# SW6124_C_LED.net
KiCad netlist of a schematic drawn in Altium Designer
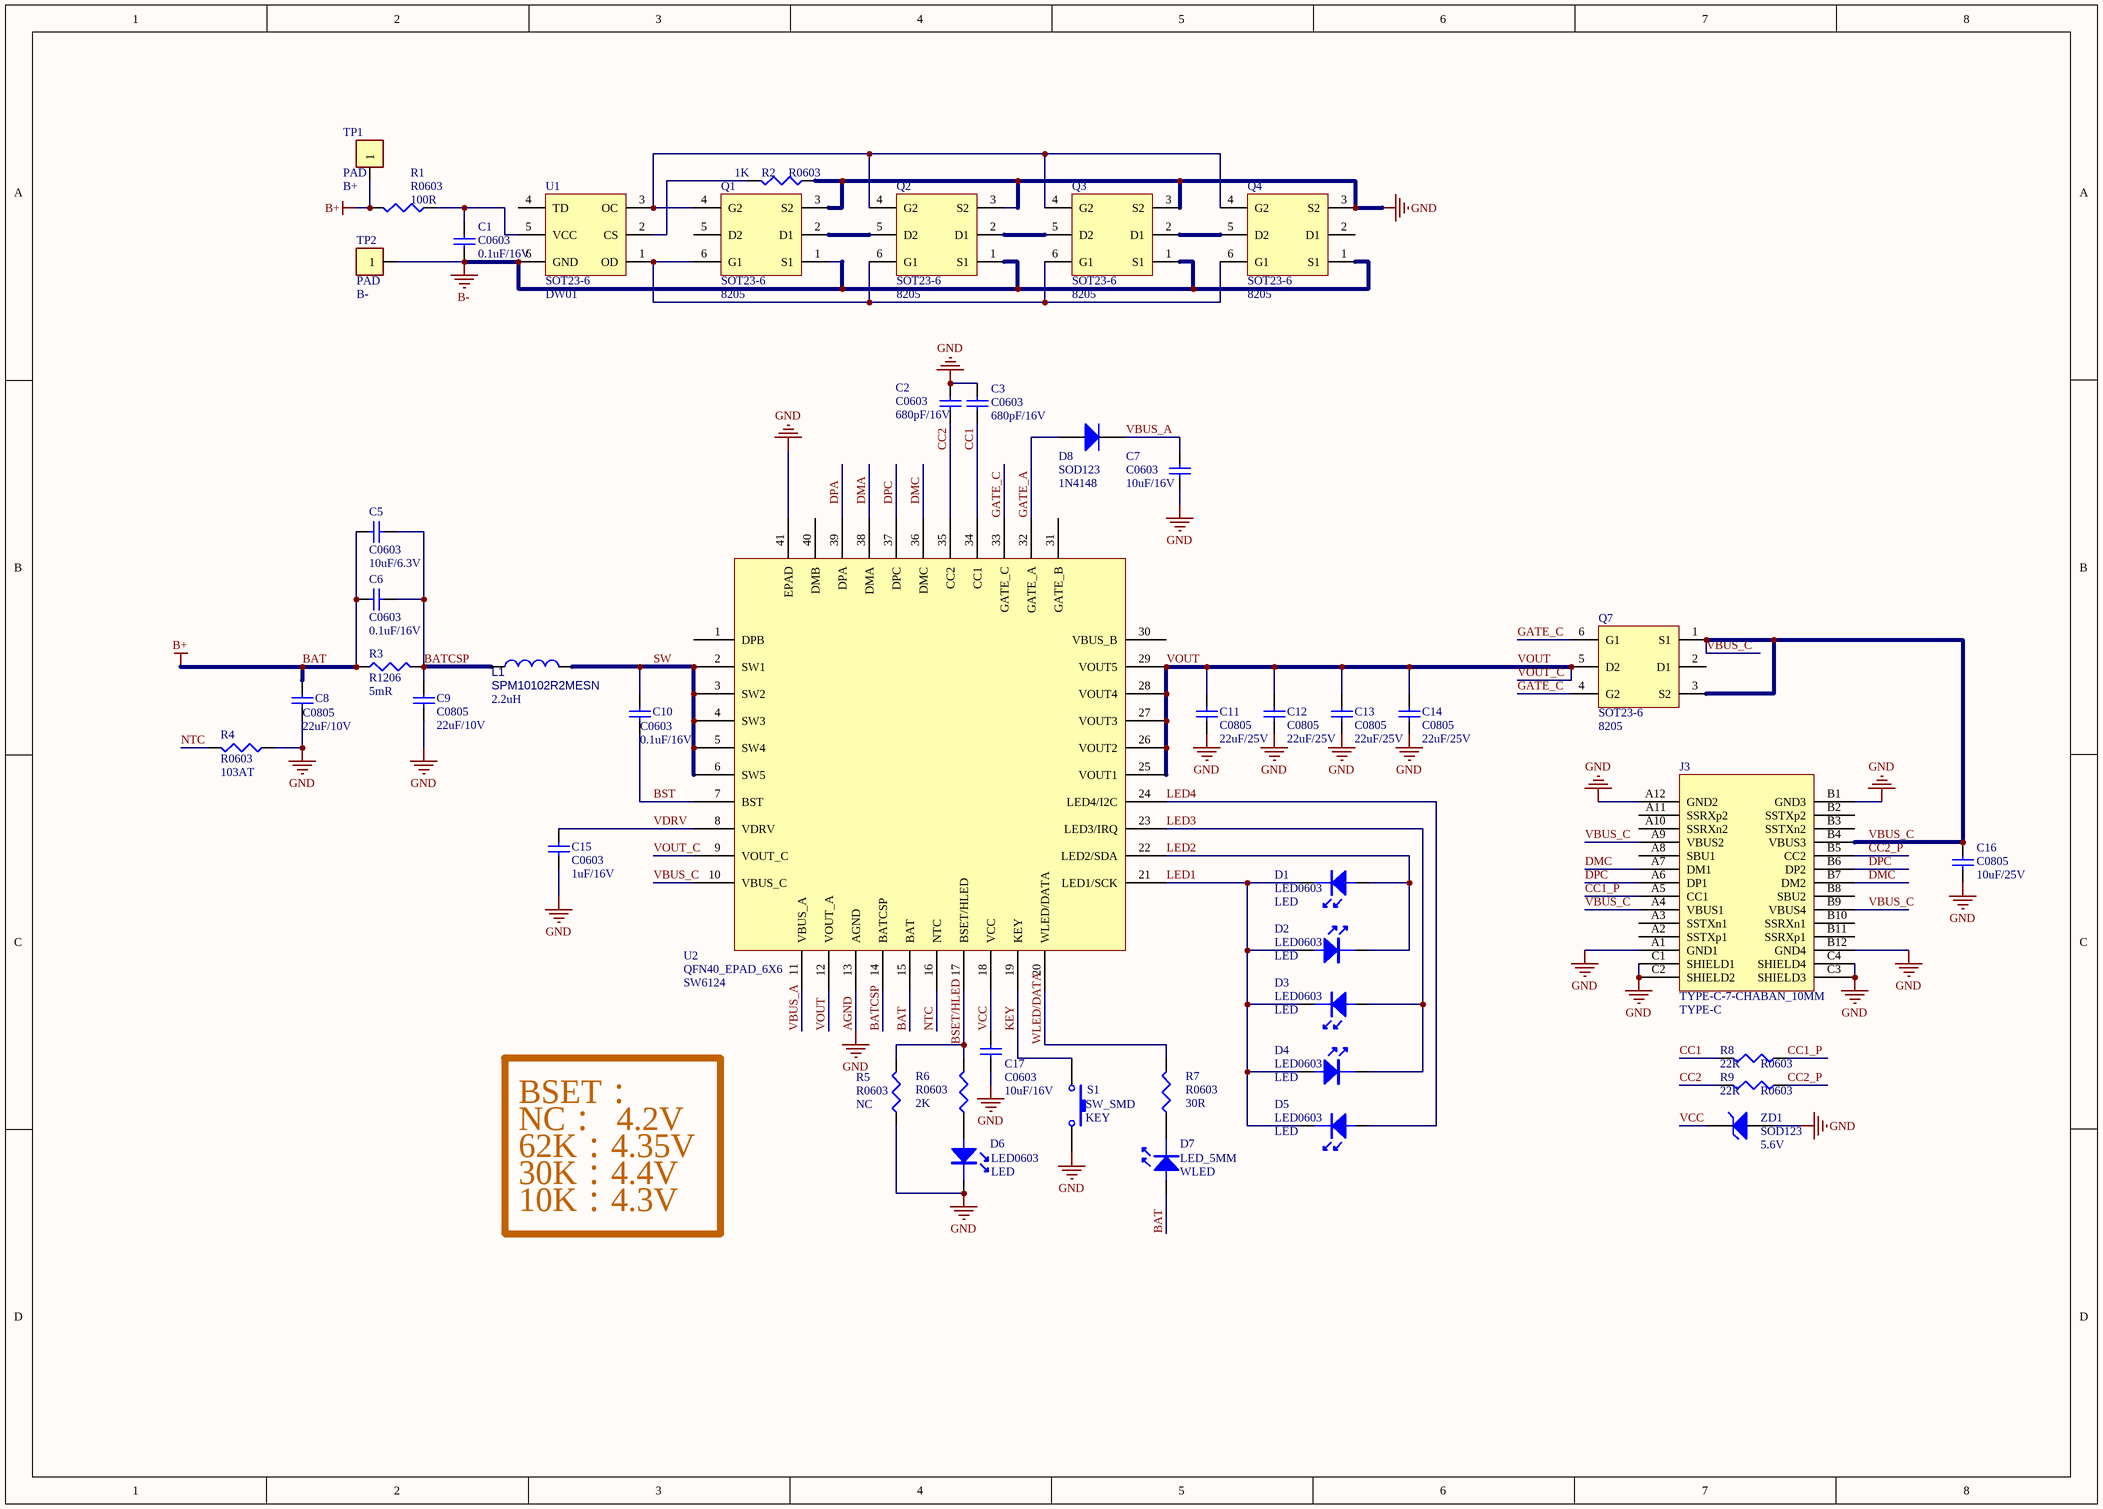
[diagram p0: SW6124+C+LED.SchDoc]

(export (version "E")
  (design (tool "Eeschema 10.0.6"))
  (components
    (comp (ref "C1")
      (value "C0603")
      (footprint "C0603")
      (description "Capacitor")
      (fields (field (name "ALTIUM_VALUE") "0.1uF/16V") (field (name "PUBLISHER") "Altium Limited"))
      (libsource (lib "*") (part "Cap"))
    )
    (comp (ref "C2")
      (value "C0603")
      (footprint "C0603")
      (description "Capacitor")
      (fields (field (name "ALTIUM_VALUE") "680pF/16V") (field (name "PUBLISHER") "Altium Limited"))
      (libsource (lib "*") (part "CAP0603"))
    )
    (comp (ref "C3")
      (value "C0603")
      (footprint "C0603")
      (description "Capacitor")
      (fields (field (name "ALTIUM_VALUE") "680pF/16V") (field (name "PUBLISHER") "Altium Limited"))
      (libsource (lib "*") (part "CAP0603"))
    )
    (comp (ref "C5")
      (value "C0603")
      (footprint "C0603")
      (description "Capacitor")
      (fields (field (name "ALTIUM_VALUE") "10uF/6.3V") (field (name "PUBLISHER") "Altium Limited"))
      (libsource (lib "*") (part "CAP0603"))
    )
    (comp (ref "C6")
      (value "C0603")
      (footprint "C0603")
      (description "Capacitor")
      (fields (field (name "ALTIUM_VALUE") "0.1uF/16V") (field (name "PUBLISHER") "Altium Limited"))
      (libsource (lib "*") (part "CAP0603"))
    )
    (comp (ref "C7")
      (value "C0603")
      (footprint "C0603")
      (description "Capacitor")
      (fields (field (name "ALTIUM_VALUE") "10uF/16V") (field (name "PUBLISHER") "Altium Limited"))
      (libsource (lib "*") (part "CAP0603"))
    )
    (comp (ref "C8")
      (value "C0805")
      (footprint "C0805")
      (description "Capacitor")
      (fields (field (name "ALTIUM_VALUE") "22uF/10V") (field (name "PUBLISHER") "Altium Limited"))
      (libsource (lib "*") (part "CAP0805"))
    )
    (comp (ref "C9")
      (value "C0805")
      (footprint "C0805")
      (description "Capacitor")
      (fields (field (name "ALTIUM_VALUE") "22uF/10V") (field (name "PUBLISHER") "Altium Limited"))
      (libsource (lib "*") (part "CAP0805"))
    )
    (comp (ref "C10")
      (value "C0603")
      (footprint "C0603")
      (description "Capacitor")
      (fields (field (name "ALTIUM_VALUE") "0.1uF/16V") (field (name "PUBLISHER") "Altium Limited"))
      (libsource (lib "*") (part "CAP0603"))
    )
    (comp (ref "C11")
      (value "C0805")
      (footprint "C0805")
      (description "Capacitor")
      (fields (field (name "ALTIUM_VALUE") "22uF/25V") (field (name "PUBLISHER") "Altium Limited"))
      (libsource (lib "*") (part "CAP0805"))
    )
    (comp (ref "C12")
      (value "C0805")
      (footprint "C0805")
      (description "Capacitor")
      (fields (field (name "ALTIUM_VALUE") "22uF/25V") (field (name "PUBLISHER") "Altium Limited"))
      (libsource (lib "*") (part "CAP0805"))
    )
    (comp (ref "C13")
      (value "C0805")
      (footprint "C0805")
      (description "Capacitor")
      (fields (field (name "ALTIUM_VALUE") "22uF/25V") (field (name "PUBLISHER") "Altium Limited"))
      (libsource (lib "*") (part "CAP0805"))
    )
    (comp (ref "C14")
      (value "C0805")
      (footprint "C0805")
      (description "Capacitor")
      (fields (field (name "ALTIUM_VALUE") "22uF/25V") (field (name "PUBLISHER") "Altium Limited"))
      (libsource (lib "*") (part "CAP0805"))
    )
    (comp (ref "C15")
      (value "C0603")
      (footprint "C0603")
      (description "Capacitor")
      (fields (field (name "ALTIUM_VALUE") "1uF/16V") (field (name "PUBLISHER") "Altium Limited"))
      (libsource (lib "*") (part "CAP0603"))
    )
    (comp (ref "C16")
      (value "C0805")
      (footprint "C0805")
      (description "Capacitor")
      (fields (field (name "ALTIUM_VALUE") "10uF/25V") (field (name "PUBLISHER") "Altium Limited"))
      (libsource (lib "*") (part "CAP0603"))
    )
    (comp (ref "C17")
      (value "C0603")
      (footprint "C0603")
      (description "Capacitor")
      (fields (field (name "ALTIUM_VALUE") "10uF/16V") (field (name "PUBLISHER") "Altium Limited"))
      (libsource (lib "*") (part "CAP0603"))
    )
    (comp (ref "D1") (value "LED") (footprint "LED0603") (libsource (lib "*") (part "LED")))
    (comp (ref "D2") (value "LED") (footprint "LED0603") (libsource (lib "*") (part "LED")))
    (comp (ref "D3") (value "LED") (footprint "LED0603") (libsource (lib "*") (part "LED")))
    (comp (ref "D4") (value "LED") (footprint "LED0603") (libsource (lib "*") (part "LED")))
    (comp (ref "D5") (value "LED") (footprint "LED0603") (libsource (lib "*") (part "LED")))
    (comp (ref "D6") (value "LED") (footprint "LED0603") (libsource (lib "*") (part "LED")))
    (comp (ref "D7")
      (value "WLED")
      (footprint "LED_5MM")
      (fields (field (name "FOOTPRINF") "LED_5MM") (field (name "Comment") "LED_5MM"))
      (libsource (lib "*") (part "LED"))
    )
    (comp (ref "D8")
      (value "1N4148")
      (footprint "SOD123")
      (description "High Conductance Fast Diode")
      (fields (field (name "Comment") "Diode 1N4148") (field (name "PUBLISHER") "Altium Limited"))
      (libsource (lib "Miscellaneous Devices") (part "Diode 1N4148"))
    )
    (comp (ref "J3")
      (value "TYPE-C")
      (footprint "TYPE-C-7-CHABAN_10MM")
      (libsource (lib "*") (part "TYPE-C"))
    )
    (comp (ref "L1")
      (value "SPM10102R2MESN")
      (footprint "INDUCTOR_SPM1010")
      (fields (field (name "ALTIUM_VALUE") "2.2uH"))
      (libsource (lib "*") (part "INDUCTOR"))
    )
    (comp (ref "Q1")
      (value "8205")
      (footprint "SOT23-6")
      (fields (field (name "FOOTPRINF") "SOT23-6"))
      (libsource (lib "") (part "8205B_1"))
    )
    (comp (ref "Q2")
      (value "8205")
      (footprint "SOT23-6")
      (fields (field (name "FOOTPRINF") "SOT23-6"))
      (libsource (lib "") (part "8205B_1"))
    )
    (comp (ref "Q3")
      (value "8205")
      (footprint "SOT23-6")
      (fields (field (name "FOOTPRINF") "SOT23-6"))
      (libsource (lib "") (part "8205B_1"))
    )
    (comp (ref "Q4")
      (value "8205")
      (footprint "SOT23-6")
      (fields (field (name "FOOTPRINF") "SOT23-6"))
      (libsource (lib "") (part "8205B_1"))
    )
    (comp (ref "Q7")
      (value "8205")
      (footprint "SOT23-6")
      (fields (field (name "FOOTPRINF") "SOT23-6"))
      (libsource (lib "*") (part "8205B"))
    )
    (comp (ref "R1")
      (value "R0603")
      (footprint "R0603")
      (description "Resistor")
      (fields (field (name "ALTIUM_VALUE") "100R") (field (name "PUBLISHER") "Altium Limited"))
      (libsource (lib "*") (part "Res3"))
    )
    (comp (ref "R2")
      (value "R0603")
      (footprint "R0603")
      (description "Resistor")
      (fields (field (name "ALTIUM_VALUE") "1K") (field (name "PUBLISHER") "Altium Limited"))
      (libsource (lib "*") (part "Res3"))
    )
    (comp (ref "R3")
      (value "R1206")
      (footprint "R1206")
      (description "Resistor")
      (fields (field (name "ALTIUM_VALUE") "5mR") (field (name "PUBLISHER") "Altium Limited"))
      (libsource (lib "*") (part "RES"))
    )
    (comp (ref "R4")
      (value "R0603")
      (footprint "R0603")
      (description "Resistor")
      (fields (field (name "ALTIUM_VALUE") "103AT") (field (name "PUBLISHER") "Altium Limited"))
      (libsource (lib "*") (part "RES"))
    )
    (comp (ref "R5")
      (value "R0603")
      (footprint "R0603")
      (description "Resistor")
      (fields (field (name "ALTIUM_VALUE") "NC") (field (name "PUBLISHER") "Altium Limited"))
      (libsource (lib "*") (part "RES"))
    )
    (comp (ref "R6")
      (value "R0603")
      (footprint "R0603")
      (description "Resistor")
      (fields (field (name "ALTIUM_VALUE") "2K") (field (name "PUBLISHER") "Altium Limited"))
      (libsource (lib "*") (part "RES"))
    )
    (comp (ref "R7")
      (value "R0603")
      (footprint "R0603")
      (description "Resistor")
      (fields (field (name "ALTIUM_VALUE") "30R") (field (name "PUBLISHER") "Altium Limited"))
      (libsource (lib "*") (part "RES"))
    )
    (comp (ref "R8")
      (value "R0603")
      (footprint "R0603")
      (description "Resistor")
      (fields (field (name "ALTIUM_VALUE") "22R") (field (name "PUBLISHER") "Altium Limited"))
      (libsource (lib "*") (part "RES"))
    )
    (comp (ref "R9")
      (value "R0603")
      (footprint "R0603")
      (description "Resistor")
      (fields (field (name "ALTIUM_VALUE") "22R") (field (name "PUBLISHER") "Altium Limited"))
      (libsource (lib "*") (part "RES"))
    )
    (comp (ref "S1")
      (value "KEY")
      (footprint "SW_SMD")
      (fields (field (name "FOOTPRINF") "SW_SMD"))
      (libsource (lib "*") (part "SW K"))
    )
    (comp (ref "TP1") (value "B+") (footprint "PAD") (libsource (lib "*") (part "Test Point")))
    (comp (ref "TP2") (value "B-") (footprint "PAD") (libsource (lib "") (part "Test Point_1")))
    (comp (ref "U1")
      (value "DW01")
      (footprint "SOT23-6")
      (fields (field (name "FOOTPRINF") "SOT23-6"))
      (libsource (lib "*") (part "DW01"))
    )
    (comp (ref "U2")
      (value "SW6124")
      (footprint "QFN40_EPAD_6X6")
      (libsource (lib "TEST") (part "SW6106_AFC"))
    )
    (comp (ref "ZD1")
      (value "SOD123")
      (footprint "SOD-123")
      (description "Zener Diode")
      (fields (field (name "ALTIUM_UNNAMED_1") "5.6V"))
      (libsource (lib "Miscellaneous Devices") (part "D Zener"))
    )
  )
  (nets
    (net (code "1") (name "/BATCSP") (class "Default")
      (node (ref "C5") (pin "2") (pinfunction "2_2") (pintype "passive"))
      (node (ref "C6") (pin "2") (pinfunction "2_2") (pintype "passive"))
      (node (ref "C9") (pin "2") (pinfunction "2_2") (pintype "passive"))
      (node (ref "L1") (pin "1") (pinfunction "1_1") (pintype "passive"))
      (node (ref "R3") (pin "2") (pinfunction "2_2") (pintype "passive"))
      (node (ref "U2") (pin "14") (pinfunction "BATCSP_14") (pintype "passive"))
    )
    (net (code "2") (name "/BSET{slash}HLED") (class "Default")
      (node (ref "R5") (pin "2") (pinfunction "2_2") (pintype "passive"))
      (node (ref "R6") (pin "2") (pinfunction "2_2") (pintype "passive"))
      (node (ref "U2") (pin "17") (pinfunction "BSET/HLED_17") (pintype "passive"))
    )
    (net (code "3") (name "/BST") (class "Default")
      (node (ref "C10") (pin "1") (pinfunction "1_1") (pintype "passive"))
      (node (ref "U2") (pin "7") (pinfunction "BST_7") (pintype "passive"))
    )
    (net (code "4") (name "/CC1") (class "Default")
      (node (ref "C3") (pin "1") (pinfunction "1_1") (pintype "passive"))
      (node (ref "R8") (pin "2") (pinfunction "2_2") (pintype "passive"))
      (node (ref "U2") (pin "34") (pinfunction "CC1_34") (pintype "passive"))
    )
    (net (code "5") (name "/CC1_P") (class "Default")
      (node (ref "J3") (pin "A5") (pinfunction "CC1_A5") (pintype "passive"))
      (node (ref "R8") (pin "1") (pinfunction "1_1") (pintype "passive"))
    )
    (net (code "6") (name "/CC2") (class "Default")
      (node (ref "C2") (pin "1") (pinfunction "1_1") (pintype "passive"))
      (node (ref "R9") (pin "2") (pinfunction "2_2") (pintype "passive"))
      (node (ref "U2") (pin "35") (pinfunction "CC2_35") (pintype "passive"))
    )
    (net (code "7") (name "/CC2_P") (class "Default")
      (node (ref "J3") (pin "B5") (pinfunction "CC2_B5") (pintype "passive"))
      (node (ref "R9") (pin "1") (pinfunction "1_1") (pintype "passive"))
    )
    (net (code "8") (name "/DMA") (class "Default")
      (node (ref "U2") (pin "38") (pinfunction "DMA_38") (pintype "passive"))
    )
    (net (code "9") (name "/DMC") (class "Default")
      (node (ref "J3") (pin "A7") (pinfunction "DM1_A7") (pintype "passive"))
      (node (ref "J3") (pin "B7") (pinfunction "DM2_B7") (pintype "passive"))
      (node (ref "U2") (pin "36") (pinfunction "DMC_36") (pintype "passive"))
    )
    (net (code "10") (name "/DPA") (class "Default")
      (node (ref "U2") (pin "39") (pinfunction "DPA_39") (pintype "passive"))
    )
    (net (code "11") (name "/DPC") (class "Default")
      (node (ref "J3") (pin "A6") (pinfunction "DP1_A6") (pintype "passive"))
      (node (ref "J3") (pin "B6") (pinfunction "DP2_B6") (pintype "passive"))
      (node (ref "U2") (pin "37") (pinfunction "DPC_37") (pintype "passive"))
    )
    (net (code "12") (name "/GATE_A") (class "Default")
      (node (ref "D8") (pin "1") (pinfunction "A_1") (pintype "passive"))
      (node (ref "U2") (pin "32") (pinfunction "GATE_A_32") (pintype "passive"))
    )
    (net (code "13") (name "/GATE_C") (class "Default")
      (node (ref "Q7") (pin "4") (pinfunction "G2_4") (pintype "passive"))
      (node (ref "Q7") (pin "6") (pinfunction "G1_6") (pintype "passive"))
      (node (ref "U2") (pin "33") (pinfunction "GATE_C_33") (pintype "passive"))
    )
    (net (code "14") (name "/KEY") (class "Default")
      (node (ref "S1") (pin "1") (pinfunction "1_1") (pintype "passive"))
      (node (ref "U2") (pin "19") (pinfunction "KEY_19") (pintype "passive"))
    )
    (net (code "15") (name "/LED1") (class "Default")
      (node (ref "D1") (pin "2") (pinfunction "K_2") (pintype "passive"))
      (node (ref "D2") (pin "1") (pinfunction "A_1") (pintype "passive"))
      (node (ref "D3") (pin "2") (pinfunction "K_2") (pintype "passive"))
      (node (ref "D4") (pin "1") (pinfunction "A_1") (pintype "passive"))
      (node (ref "D5") (pin "2") (pinfunction "K_2") (pintype "passive"))
      (node (ref "U2") (pin "21") (pinfunction "LED1/SCK_21") (pintype "passive"))
    )
    (net (code "16") (name "/LED2") (class "Default")
      (node (ref "D1") (pin "1") (pinfunction "A_1") (pintype "passive"))
      (node (ref "D2") (pin "2") (pinfunction "K_2") (pintype "passive"))
      (node (ref "U2") (pin "22") (pinfunction "LED2/SDA_22") (pintype "passive"))
    )
    (net (code "17") (name "/LED3") (class "Default")
      (node (ref "D3") (pin "1") (pinfunction "A_1") (pintype "passive"))
      (node (ref "D4") (pin "2") (pinfunction "K_2") (pintype "passive"))
      (node (ref "U2") (pin "23") (pinfunction "LED3/IRQ_23") (pintype "passive"))
    )
    (net (code "18") (name "/LED4") (class "Default")
      (node (ref "D5") (pin "1") (pinfunction "A_1") (pintype "passive"))
      (node (ref "U2") (pin "24") (pinfunction "LED4/I2C_24") (pintype "passive"))
    )
    (net (code "19") (name "/NTC") (class "Default")
      (node (ref "R4") (pin "2") (pinfunction "2_2") (pintype "passive"))
      (node (ref "U2") (pin "16") (pinfunction "NTC_16") (pintype "passive"))
    )
    (net (code "20") (name "/SW") (class "Default")
      (node (ref "C10") (pin "2") (pinfunction "2_2") (pintype "passive"))
      (node (ref "L1") (pin "2") (pinfunction "2_2") (pintype "passive"))
      (node (ref "U2") (pin "2") (pinfunction "SW1_2") (pintype "passive"))
      (node (ref "U2") (pin "3") (pinfunction "SW2_3") (pintype "passive"))
      (node (ref "U2") (pin "4") (pinfunction "SW3_4") (pintype "passive"))
      (node (ref "U2") (pin "5") (pinfunction "SW4_5") (pintype "passive"))
      (node (ref "U2") (pin "6") (pinfunction "SW5_6") (pintype "passive"))
    )
    (net (code "21") (name "/VBUS_A") (class "Default")
      (node (ref "C7") (pin "2") (pinfunction "2_2") (pintype "passive"))
      (node (ref "D8") (pin "2") (pinfunction "K_2") (pintype "passive"))
      (node (ref "U2") (pin "11") (pinfunction "VBUS_A_11") (pintype "passive"))
    )
    (net (code "22") (name "/VBUS_C") (class "Default")
      (node (ref "C16") (pin "2") (pinfunction "2_2") (pintype "passive"))
      (node (ref "J3") (pin "A4") (pinfunction "VBUS1_A4") (pintype "passive"))
      (node (ref "J3") (pin "A9") (pinfunction "VBUS2_A9") (pintype "passive"))
      (node (ref "J3") (pin "B4") (pinfunction "VBUS3_B4") (pintype "passive"))
      (node (ref "J3") (pin "B9") (pinfunction "VBUS4_B9") (pintype "passive"))
      (node (ref "Q7") (pin "1") (pinfunction "S1_1") (pintype "passive"))
      (node (ref "Q7") (pin "3") (pinfunction "S2_3") (pintype "passive"))
      (node (ref "U2") (pin "10") (pinfunction "VBUS_C_10") (pintype "passive"))
    )
    (net (code "23") (name "/VCC") (class "Default")
      (node (ref "C17") (pin "2") (pinfunction "2_2") (pintype "passive"))
      (node (ref "U2") (pin "18") (pinfunction "VCC_18") (pintype "passive"))
      (node (ref "ZD1") (pin "2") (pinfunction "K_2") (pintype "passive"))
    )
    (net (code "24") (name "/VDRV") (class "Default")
      (node (ref "C15") (pin "2") (pinfunction "2_2") (pintype "passive"))
      (node (ref "U2") (pin "8") (pinfunction "VDRV_8") (pintype "passive"))
    )
    (net (code "25") (name "/VOUT") (class "Default")
      (node (ref "C11") (pin "2") (pinfunction "2_2") (pintype "passive"))
      (node (ref "C12") (pin "2") (pinfunction "2_2") (pintype "passive"))
      (node (ref "C13") (pin "2") (pinfunction "2_2") (pintype "passive"))
      (node (ref "C14") (pin "2") (pinfunction "2_2") (pintype "passive"))
      (node (ref "Q7") (pin "5") (pinfunction "D2_5") (pintype "passive"))
      (node (ref "U2") (pin "12") (pinfunction "VOUT_A_12") (pintype "passive"))
      (node (ref "U2") (pin "25") (pinfunction "VOUT1_25") (pintype "passive"))
      (node (ref "U2") (pin "26") (pinfunction "VOUT2_26") (pintype "passive"))
      (node (ref "U2") (pin "27") (pinfunction "VOUT3_27") (pintype "passive"))
      (node (ref "U2") (pin "28") (pinfunction "VOUT4_28") (pintype "passive"))
      (node (ref "U2") (pin "29") (pinfunction "VOUT5_29") (pintype "passive"))
      (node (ref "U2") (pin "9") (pinfunction "VOUT_C_9") (pintype "passive"))
    )
    (net (code "26") (name "/WLED{slash}DATA") (class "Default")
      (node (ref "R7") (pin "2") (pinfunction "2_2") (pintype "passive"))
      (node (ref "U2") (pin "20") (pinfunction "WLED/DATA_20") (pintype "passive"))
    )
    (net (code "27") (name "B+") (class "Default")
      (node (ref "C5") (pin "1") (pinfunction "1_1") (pintype "passive"))
      (node (ref "C6") (pin "1") (pinfunction "1_1") (pintype "passive"))
      (node (ref "C8") (pin "2") (pinfunction "2_2") (pintype "passive"))
      (node (ref "D7") (pin "1") (pinfunction "A_1") (pintype "passive"))
      (node (ref "R1") (pin "2") (pinfunction "2_2") (pintype "passive"))
      (node (ref "R3") (pin "1") (pinfunction "1_1") (pintype "passive"))
      (node (ref "TP1") (pin "1") (pinfunction "1_1") (pintype "passive"))
      (node (ref "U2") (pin "15") (pinfunction "BAT_15") (pintype "passive"))
    )
    (net (code "28") (name "B-") (class "Default")
      (node (ref "C1") (pin "1") (pinfunction "1_1") (pintype "passive"))
      (node (ref "Q1") (pin "1") (pinfunction "S1_1") (pintype "passive"))
      (node (ref "Q2") (pin "1") (pinfunction "S1_1") (pintype "passive"))
      (node (ref "Q3") (pin "1") (pinfunction "S1_1") (pintype "passive"))
      (node (ref "Q4") (pin "1") (pinfunction "S1_1") (pintype "passive"))
      (node (ref "TP2") (pin "1") (pinfunction "1_1") (pintype "passive"))
      (node (ref "U1") (pin "6") (pinfunction "GND_6") (pintype "passive"))
    )
    (net (code "29") (name "GND") (class "Default")
      (node (ref "C11") (pin "1") (pinfunction "1_1") (pintype "passive"))
      (node (ref "C12") (pin "1") (pinfunction "1_1") (pintype "passive"))
      (node (ref "C13") (pin "1") (pinfunction "1_1") (pintype "passive"))
      (node (ref "C14") (pin "1") (pinfunction "1_1") (pintype "passive"))
      (node (ref "C15") (pin "1") (pinfunction "1_1") (pintype "passive"))
      (node (ref "C16") (pin "1") (pinfunction "1_1") (pintype "passive"))
      (node (ref "C17") (pin "1") (pinfunction "1_1") (pintype "passive"))
      (node (ref "C2") (pin "2") (pinfunction "2_2") (pintype "passive"))
      (node (ref "C3") (pin "2") (pinfunction "2_2") (pintype "passive"))
      (node (ref "C7") (pin "1") (pinfunction "1_1") (pintype "passive"))
      (node (ref "C8") (pin "1") (pinfunction "1_1") (pintype "passive"))
      (node (ref "C9") (pin "1") (pinfunction "1_1") (pintype "passive"))
      (node (ref "D6") (pin "2") (pinfunction "K_2") (pintype "passive"))
      (node (ref "J3") (pin "A1") (pinfunction "GND1_A1") (pintype "passive"))
      (node (ref "J3") (pin "A12") (pinfunction "GND2_A12") (pintype "passive"))
      (node (ref "J3") (pin "B1") (pinfunction "GND3_B1") (pintype "passive"))
      (node (ref "J3") (pin "B12") (pinfunction "GND4_B12") (pintype "passive"))
      (node (ref "J3") (pin "C1") (pinfunction "SHIELD1_C1") (pintype "passive"))
      (node (ref "J3") (pin "C2") (pinfunction "SHIELD2_C2") (pintype "passive"))
      (node (ref "J3") (pin "C3") (pinfunction "SHIELD3_C3") (pintype "passive"))
      (node (ref "J3") (pin "C4") (pinfunction "SHIELD4_C4") (pintype "passive"))
      (node (ref "Q1") (pin "3") (pinfunction "S2_3") (pintype "passive"))
      (node (ref "Q2") (pin "3") (pinfunction "S2_3") (pintype "passive"))
      (node (ref "Q3") (pin "3") (pinfunction "S2_3") (pintype "passive"))
      (node (ref "Q4") (pin "3") (pinfunction "S2_3") (pintype "passive"))
      (node (ref "R2") (pin "1") (pinfunction "1_1") (pintype "passive"))
      (node (ref "R4") (pin "1") (pinfunction "1_1") (pintype "passive"))
      (node (ref "R5") (pin "1") (pinfunction "1_1") (pintype "passive"))
      (node (ref "S1") (pin "2") (pinfunction "2_2") (pintype "passive"))
      (node (ref "U2") (pin "13") (pinfunction "AGND_13") (pintype "passive"))
      (node (ref "U2") (pin "41") (pinfunction "EPAD_41") (pintype "passive"))
      (node (ref "ZD1") (pin "1") (pinfunction "A_1") (pintype "passive"))
    )
    (net (code "30") (name "Net-(D6-A)") (class "Default")
      (node (ref "D6") (pin "1") (pinfunction "A_1") (pintype "passive"))
      (node (ref "R6") (pin "1") (pinfunction "1_1") (pintype "passive"))
    )
    (net (code "31") (name "Net-(D7-K)") (class "Default")
      (node (ref "D7") (pin "2") (pinfunction "K_2") (pintype "passive"))
      (node (ref "R7") (pin "1") (pinfunction "1_1") (pintype "passive"))
    )
    (net (code "32") (name "Net-(Q1-D1)") (class "Default")
      (node (ref "Q1") (pin "2") (pinfunction "D1_2") (pintype "passive"))
      (node (ref "Q2") (pin "5") (pinfunction "D2_5") (pintype "passive"))
    )
    (net (code "33") (name "Net-(Q1-G1)") (class "Default")
      (node (ref "Q1") (pin "6") (pinfunction "G1_6") (pintype "passive"))
      (node (ref "Q2") (pin "6") (pinfunction "G1_6") (pintype "passive"))
      (node (ref "Q3") (pin "6") (pinfunction "G1_6") (pintype "passive"))
      (node (ref "Q4") (pin "6") (pinfunction "G1_6") (pintype "passive"))
      (node (ref "U1") (pin "1") (pinfunction "OD_1") (pintype "passive"))
    )
    (net (code "34") (name "Net-(Q1-G2)") (class "Default")
      (node (ref "Q1") (pin "4") (pinfunction "G2_4") (pintype "passive"))
      (node (ref "Q2") (pin "4") (pinfunction "G2_4") (pintype "passive"))
      (node (ref "Q3") (pin "4") (pinfunction "G2_4") (pintype "passive"))
      (node (ref "Q4") (pin "4") (pinfunction "G2_4") (pintype "passive"))
      (node (ref "U1") (pin "3") (pinfunction "OC_3") (pintype "passive"))
    )
    (net (code "35") (name "Net-(Q2-D1)") (class "Default")
      (node (ref "Q2") (pin "2") (pinfunction "D1_2") (pintype "passive"))
      (node (ref "Q3") (pin "5") (pinfunction "D2_5") (pintype "passive"))
    )
    (net (code "36") (name "Net-(Q3-D1)") (class "Default")
      (node (ref "Q3") (pin "2") (pinfunction "D1_2") (pintype "passive"))
      (node (ref "Q4") (pin "5") (pinfunction "D2_5") (pintype "passive"))
    )
    (net (code "37") (name "Net-(U1-CS)") (class "Default")
      (node (ref "R2") (pin "2") (pinfunction "2_2") (pintype "passive"))
      (node (ref "U1") (pin "2") (pinfunction "CS_2") (pintype "passive"))
    )
    (net (code "38") (name "Net-(U1-VCC)") (class "Default")
      (node (ref "C1") (pin "2") (pinfunction "2_2") (pintype "passive"))
      (node (ref "R1") (pin "1") (pinfunction "1_1") (pintype "passive"))
      (node (ref "U1") (pin "5") (pinfunction "VCC_5") (pintype "passive"))
    )
    (net (code "39") (name "unconnected-(J3-SBU1-PadA8)") (class "Default")
      (node (ref "J3") (pin "A8") (pinfunction "SBU1_A8") (pintype "passive"))
    )
    (net (code "40") (name "unconnected-(J3-SBU2-PadB8)") (class "Default")
      (node (ref "J3") (pin "B8") (pinfunction "SBU2_B8") (pintype "passive"))
    )
    (net (code "41") (name "unconnected-(J3-SSRXn1-PadB10)") (class "Default")
      (node (ref "J3") (pin "B10") (pinfunction "SSRXn1_B10") (pintype "passive"))
    )
    (net (code "42") (name "unconnected-(J3-SSRXn2-PadA10)") (class "Default")
      (node (ref "J3") (pin "A10") (pinfunction "SSRXn2_A10") (pintype "passive"))
    )
    (net (code "43") (name "unconnected-(J3-SSRXp1-PadB11)") (class "Default")
      (node (ref "J3") (pin "B11") (pinfunction "SSRXp1_B11") (pintype "passive"))
    )
    (net (code "44") (name "unconnected-(J3-SSRXp2-PadA11)") (class "Default")
      (node (ref "J3") (pin "A11") (pinfunction "SSRXp2_A11") (pintype "passive"))
    )
    (net (code "45") (name "unconnected-(J3-SSTXn1-PadA3)") (class "Default")
      (node (ref "J3") (pin "A3") (pinfunction "SSTXn1_A3") (pintype "passive"))
    )
    (net (code "46") (name "unconnected-(J3-SSTXn2-PadB3)") (class "Default")
      (node (ref "J3") (pin "B3") (pinfunction "SSTXn2_B3") (pintype "passive"))
    )
    (net (code "47") (name "unconnected-(J3-SSTXp1-PadA2)") (class "Default")
      (node (ref "J3") (pin "A2") (pinfunction "SSTXp1_A2") (pintype "passive"))
    )
    (net (code "48") (name "unconnected-(J3-SSTXp2-PadB2)") (class "Default")
      (node (ref "J3") (pin "B2") (pinfunction "SSTXp2_B2") (pintype "passive"))
    )
    (net (code "49") (name "unconnected-(Q1-D2-Pad5)") (class "Default")
      (node (ref "Q1") (pin "5") (pinfunction "D2_5") (pintype "passive"))
    )
    (net (code "50") (name "unconnected-(Q4-D1-Pad2)") (class "Default")
      (node (ref "Q4") (pin "2") (pinfunction "D1_2") (pintype "passive"))
    )
    (net (code "51") (name "unconnected-(Q7-D1-Pad2)") (class "Default")
      (node (ref "Q7") (pin "2") (pinfunction "D1_2") (pintype "passive"))
    )
    (net (code "52") (name "unconnected-(U1-TD-Pad4)") (class "Default")
      (node (ref "U1") (pin "4") (pinfunction "TD_4") (pintype "passive"))
    )
    (net (code "53") (name "unconnected-(U2-DMB-Pad40)") (class "Default")
      (node (ref "U2") (pin "40") (pinfunction "DMB_40") (pintype "passive"))
    )
    (net (code "54") (name "unconnected-(U2-DPB-Pad1)") (class "Default")
      (node (ref "U2") (pin "1") (pinfunction "DPB_1") (pintype "passive"))
    )
    (net (code "55") (name "unconnected-(U2-GATE_B-Pad31)") (class "Default")
      (node (ref "U2") (pin "31") (pinfunction "GATE_B_31") (pintype "passive"))
    )
    (net (code "56") (name "unconnected-(U2-VBUS_B-Pad30)") (class "Default")
      (node (ref "U2") (pin "30") (pinfunction "VBUS_B_30") (pintype "passive"))
    )
  )
)
